# Encoder.net
KiCad netlist of a schematic drawn in Altium Designer
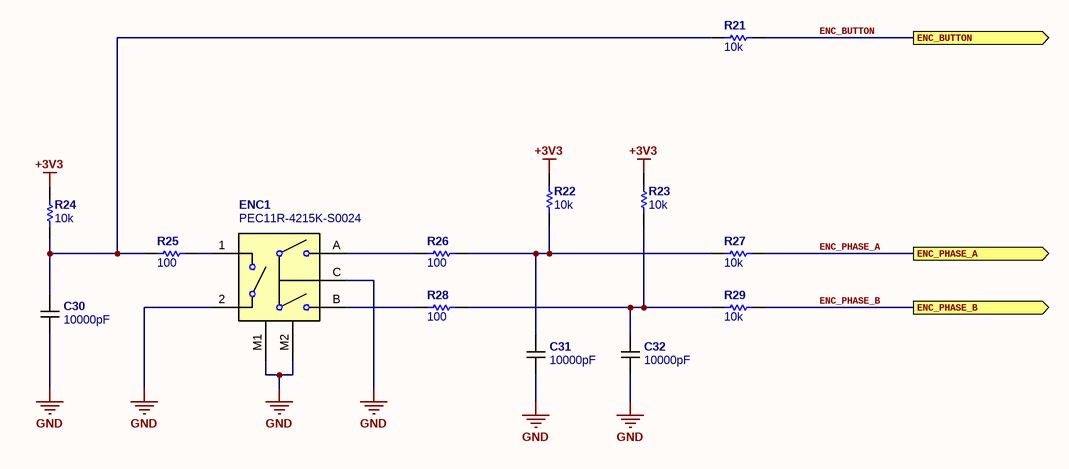
[diagram p0: Encoder.SchDoc]

(export (version "E")
  (design (tool "Eeschema 10.0.6"))
  (components
    (comp (ref "C30")
      (value "10000pF")
      (footprint "C0603_0.90MM_HD")
      (description "CAP CER 10000PF 50V C0G 0603")
      (fields
        (field (name "MANUFACTURER PART NUMBER") "CGA3E2C0G1H103J080AA")
        (field (name "MANUFACTURER") "TDK Corporation")
      )
      (libsource (lib "Capacitors - TDK- AEC-Q200") (part "C_2P_NP"))
    )
    (comp (ref "C31")
      (value "10000pF")
      (footprint "C0603_0.90MM_HD")
      (description "CAP CER 10000PF 50V C0G 0603")
      (fields
        (field (name "MANUFACTURER PART NUMBER") "CGA3E2C0G1H103J080AA")
        (field (name "MANUFACTURER") "TDK Corporation")
      )
      (libsource (lib "Capacitors - TDK- AEC-Q200") (part "C_2P_NP"))
    )
    (comp (ref "C32")
      (value "10000pF")
      (footprint "C0603_0.90MM_HD")
      (description "CAP CER 10000PF 50V C0G 0603")
      (fields
        (field (name "MANUFACTURER PART NUMBER") "CGA3E2C0G1H103J080AA")
        (field (name "MANUFACTURER") "TDK Corporation")
      )
      (libsource (lib "Capacitors - TDK- AEC-Q200") (part "C_2P_NP"))
    )
    (comp (ref "ENC1")
      (value "PEC11R-4215K-S0024")
      (footprint "PEC11R-4215K-S0024")
      (description "Encoders 15mm SHAFT w/SWITCH")
      (fields (field (name "MANUFACTURER") "Bourns"))
      (libsource (lib "eElectroMechanical") (part "PEC11R-4215K-S0024"))
    )
    (comp (ref "R21")
      (value "10k")
      (footprint "R0603_0.55MM_MD")
      (description "RES 10K OHM 1/10W 1% 0603 SMD")
      (fields
        (field (name "MANUFACTURER PART NUMBER") "ERJ-3EKF1002V")
        (field (name "MANUFACTURER") "Panasonic Electronic Components")
      )
      (libsource (lib "Resistors - Panasonic - AEC-Q200") (part "R_2P"))
    )
    (comp (ref "R22")
      (value "10k")
      (footprint "R0603_0.55MM_MD")
      (description "RES 10K OHM 1/10W 1% 0603 SMD")
      (fields
        (field (name "MANUFACTURER PART NUMBER") "ERJ-3EKF1002V")
        (field (name "MANUFACTURER") "Panasonic Electronic Components")
      )
      (libsource (lib "Resistors - Panasonic - AEC-Q200") (part "R_2P"))
    )
    (comp (ref "R23")
      (value "10k")
      (footprint "R0603_0.55MM_MD")
      (description "RES 10K OHM 1/10W 1% 0603 SMD")
      (fields
        (field (name "MANUFACTURER PART NUMBER") "ERJ-3EKF1002V")
        (field (name "MANUFACTURER") "Panasonic Electronic Components")
      )
      (libsource (lib "Resistors - Panasonic - AEC-Q200") (part "R_2P"))
    )
    (comp (ref "R24")
      (value "10k")
      (footprint "R0603_0.55MM_MD")
      (description "RES 10K OHM 1/10W 1% 0603 SMD")
      (fields
        (field (name "MANUFACTURER PART NUMBER") "ERJ-3EKF1002V")
        (field (name "MANUFACTURER") "Panasonic Electronic Components")
      )
      (libsource (lib "Resistors - Panasonic - AEC-Q200") (part "R_2P"))
    )
    (comp (ref "R25")
      (value "100")
      (footprint "R0603_0.55MM_MD")
      (description "RES 100 OHM 1/10W 1% 0603 SMD")
      (fields
        (field (name "MANUFACTURER PART NUMBER") "ERJ-3EKF1000V")
        (field (name "MANUFACTURER") "Panasonic Electronic Components")
      )
      (libsource (lib "Resistors - Panasonic - AEC-Q200") (part "R_2P"))
    )
    (comp (ref "R26")
      (value "100")
      (footprint "R0603_0.55MM_MD")
      (description "RES 100 OHM 1/10W 1% 0603 SMD")
      (fields
        (field (name "MANUFACTURER PART NUMBER") "ERJ-3EKF1000V")
        (field (name "MANUFACTURER") "Panasonic Electronic Components")
      )
      (libsource (lib "Resistors - Panasonic - AEC-Q200") (part "R_2P"))
    )
    (comp (ref "R27")
      (value "10k")
      (footprint "R0603_0.55MM_MD")
      (description "RES 10K OHM 1/10W 1% 0603 SMD")
      (fields
        (field (name "MANUFACTURER PART NUMBER") "ERJ-3EKF1002V")
        (field (name "MANUFACTURER") "Panasonic Electronic Components")
      )
      (libsource (lib "Resistors - Panasonic - AEC-Q200") (part "R_2P"))
    )
    (comp (ref "R28")
      (value "100")
      (footprint "R0603_0.55MM_MD")
      (description "RES 100 OHM 1/10W 1% 0603 SMD")
      (fields
        (field (name "MANUFACTURER PART NUMBER") "ERJ-3EKF1000V")
        (field (name "MANUFACTURER") "Panasonic Electronic Components")
      )
      (libsource (lib "Resistors - Panasonic - AEC-Q200") (part "R_2P"))
    )
    (comp (ref "R29")
      (value "10k")
      (footprint "R0603_0.55MM_MD")
      (description "RES 10K OHM 1/10W 1% 0603 SMD")
      (fields
        (field (name "MANUFACTURER PART NUMBER") "ERJ-3EKF1002V")
        (field (name "MANUFACTURER") "Panasonic Electronic Components")
      )
      (libsource (lib "Resistors - Panasonic - AEC-Q200") (part "R_2P"))
    )
  )
  (nets
    (net (code "1") (name "+3V3") (class "Default")
      (node (ref "R22") (pin "2") (pinfunction "2_2") (pintype "passive"))
      (node (ref "R23") (pin "2") (pinfunction "2_2") (pintype "passive"))
      (node (ref "R24") (pin "2") (pinfunction "2_2") (pintype "passive"))
    )
    (net (code "2") (name "/ENC_BUTTON") (class "Default")
      (node (ref "R21") (pin "1") (pinfunction "1_1") (pintype "passive"))
    )
    (net (code "3") (name "/ENC_PHASE_A") (class "Default")
      (node (ref "R27") (pin "1") (pinfunction "1_1") (pintype "passive"))
    )
    (net (code "4") (name "/ENC_PHASE_B") (class "Default")
      (node (ref "R29") (pin "1") (pinfunction "1_1") (pintype "passive"))
    )
    (net (code "5") (name "GND") (class "Default")
      (node (ref "C30") (pin "1") (pinfunction "1_1") (pintype "passive"))
      (node (ref "C31") (pin "1") (pinfunction "1_1") (pintype "passive"))
      (node (ref "C32") (pin "1") (pinfunction "1_1") (pintype "passive"))
      (node (ref "ENC1") (pin "2") (pinfunction "2_2") (pintype "passive"))
      (node (ref "ENC1") (pin "C") (pinfunction "C_C") (pintype "passive"))
      (node (ref "ENC1") (pin "M1") (pinfunction "M1_M1") (pintype "passive"))
      (node (ref "ENC1") (pin "M2") (pinfunction "M2_M2") (pintype "passive"))
    )
    (net (code "6") (name "Net-(C30-1-Pad2)") (class "Default")
      (node (ref "C30") (pin "2") (pinfunction "1_2") (pintype "passive"))
      (node (ref "R21") (pin "2") (pinfunction "2_2") (pintype "passive"))
      (node (ref "R24") (pin "1") (pinfunction "1_1") (pintype "passive"))
      (node (ref "R25") (pin "2") (pinfunction "2_2") (pintype "passive"))
    )
    (net (code "7") (name "Net-(C31-1-Pad2)") (class "Default")
      (node (ref "C31") (pin "2") (pinfunction "1_2") (pintype "passive"))
      (node (ref "R22") (pin "1") (pinfunction "1_1") (pintype "passive"))
      (node (ref "R26") (pin "1") (pinfunction "1_1") (pintype "passive"))
      (node (ref "R27") (pin "2") (pinfunction "2_2") (pintype "passive"))
    )
    (net (code "8") (name "Net-(C32-1-Pad2)") (class "Default")
      (node (ref "C32") (pin "2") (pinfunction "1_2") (pintype "passive"))
      (node (ref "R23") (pin "1") (pinfunction "1_1") (pintype "passive"))
      (node (ref "R28") (pin "1") (pinfunction "1_1") (pintype "passive"))
      (node (ref "R29") (pin "2") (pinfunction "2_2") (pintype "passive"))
    )
    (net (code "9") (name "Net-(ENC1-Pad1)") (class "Default")
      (node (ref "ENC1") (pin "1") (pinfunction "1_1") (pintype "passive"))
      (node (ref "R25") (pin "1") (pinfunction "1_1") (pintype "passive"))
    )
    (net (code "10") (name "Net-(ENC1-PadA)") (class "Default")
      (node (ref "ENC1") (pin "A") (pinfunction "A_A") (pintype "passive"))
      (node (ref "R26") (pin "2") (pinfunction "2_2") (pintype "passive"))
    )
    (net (code "11") (name "Net-(ENC1-PadB)") (class "Default")
      (node (ref "ENC1") (pin "B") (pinfunction "B_B") (pintype "passive"))
      (node (ref "R28") (pin "2") (pinfunction "2_2") (pintype "passive"))
    )
  )
)
